# VoltageRegulators.net
KiCad netlist of a schematic drawn in Altium Designer
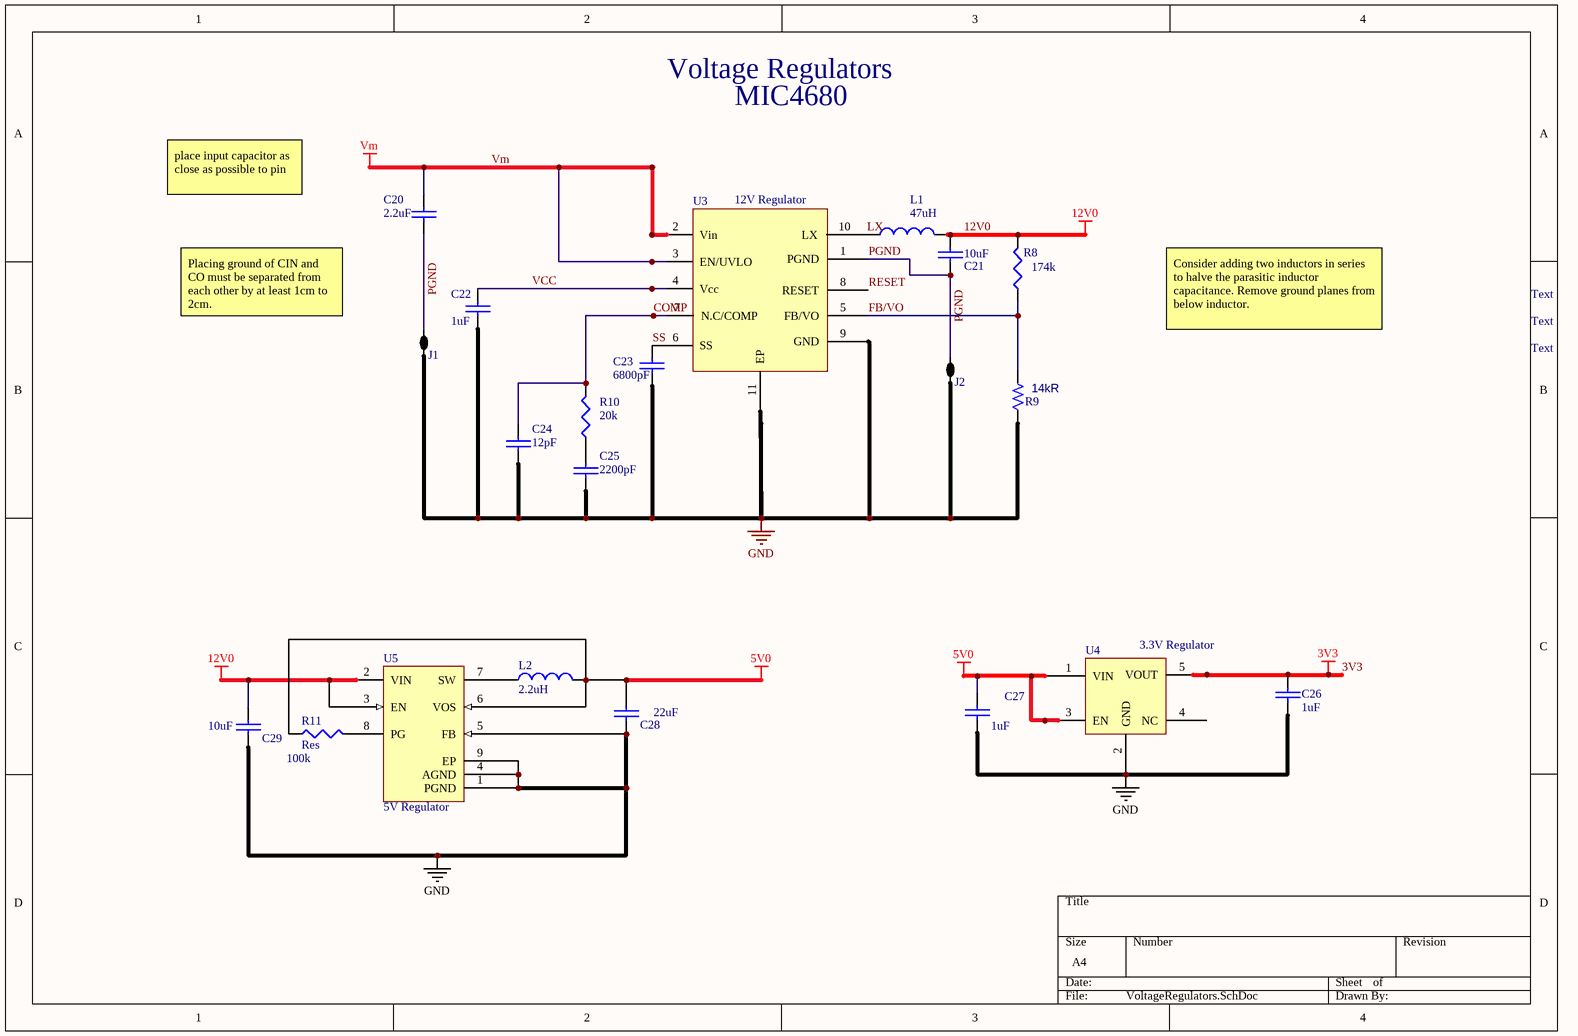
[diagram p0: VoltageRegulators.SchDoc]

(export (version "E")
  (design (tool "Eeschema 10.0.6"))
  (components
    (comp (ref "C20")
      (value "2.2uF")
      (footprint "CAP0805")
      (description "Capacitor")
      (fields
        (field (name "MANUFACTURER") "TDK Corporation")
        (field (name "MANUFACTURER PART NUMBER") "C2012X7R1V225K085AC")
      )
      (libsource (lib "BPL-ShematicLibrary") (part "Capacitor"))
    )
    (comp (ref "C21")
      (value "10uF")
      (footprint "CAP1210")
      (description "Capacitor")
      (fields
        (field (name "MANUFACTURER") "KEMET")
        (field (name "MANUFACTURER PART NUMBER") "C1210C106K9RAC7800")
      )
      (libsource (lib "BPL-ShematicLibrary") (part "Capacitor"))
    )
    (comp (ref "C22")
      (value "1uF")
      (footprint "CAP0402")
      (description "Capacitor")
      (fields
        (field (name "MANUFACTURER") "TDK Corporation")
        (field (name "MANUFACTURER PART NUMBER") "C1005X5R1V105K050BC")
      )
      (libsource (lib "BPL-ShematicLibrary") (part "Capacitor"))
    )
    (comp (ref "C23")
      (value "6800pF")
      (footprint "CAP0402")
      (description "Capacitor")
      (fields
        (field (name "MANUFACTURER") "KEMET")
        (field (name "MANUFACTURER PART NUMBER") "C0402C682J5RACTU")
      )
      (libsource (lib "BPL-ShematicLibrary") (part "Capacitor"))
    )
    (comp (ref "C24")
      (value "12pF")
      (footprint "CAP0402")
      (description "Capacitor")
      (fields
        (field (name "MANUFACTURER") "KEMET")
        (field (name "MANUFACTURER PART NUMBER") "C0402C120J3GACAUTO")
      )
      (libsource (lib "BPL-ShematicLibrary") (part "Capacitor"))
    )
    (comp (ref "C25")
      (value "2200pF")
      (footprint "CAP0402")
      (description "Capacitor")
      (fields
        (field (name "MANUFACTURER") "Murata Electronics North America")
        (field (name "MANUFACTURER PART NUMBER") "GRM155R71H222KA01D")
      )
      (libsource (lib "BPL-ShematicLibrary") (part "Capacitor"))
    )
    (comp (ref "C26")
      (value "1uF")
      (footprint "CAP0402")
      (description "Capacitor")
      (fields
        (field (name "MANUFACTURER") "TDK Corporation")
        (field (name "MANUFACTURER PART NUMBER") "C1005X5R1V105K050BC")
      )
      (libsource (lib "BPL-ShematicLibrary") (part "Capacitor"))
    )
    (comp (ref "C27")
      (value "1uF")
      (footprint "CAP0402")
      (description "Capacitor")
      (fields
        (field (name "MANUFACTURER") "TDK Corporation")
        (field (name "MANUFACTURER PART NUMBER") "C1005X5R1V105K050BC")
      )
      (libsource (lib "BPL-ShematicLibrary") (part "Capacitor"))
    )
    (comp (ref "C28")
      (value "22uF")
      (footprint "CAP0805")
      (description "Capacitor")
      (fields
        (field (name "MANUFACTURER") "TDK Corporation")
        (field (name "MANUFACTURER PART NUMBER") "C2012X5R0J226K125AB")
      )
      (libsource (lib "BPL-ShematicLibrary") (part "Capacitor"))
    )
    (comp (ref "C29")
      (value "10uF")
      (footprint "CAP0805")
      (description "Capacitor")
      (fields
        (field (name "MANUFACTURER") "Murata Electronics North America")
        (field (name "MANUFACTURER PART NUMBER") "GRM21BR61E106MA73L")
      )
      (libsource (lib "BPL-ShematicLibrary") (part "Capacitor"))
    )
    (comp (ref "J1")
      (value "2 way net tie junction")
      (footprint "2way_LP")
      (libsource (lib "NetTieLib") (part "2way"))
    )
    (comp (ref "J2")
      (value "2 way net tie junction")
      (footprint "2way_LP")
      (libsource (lib "NetTieLib") (part "2way"))
    )
    (comp (ref "L1")
      (value "47uH")
      (footprint "74404064470")
      (description "FIXED IND 47UH 1.2A 200 MOHM SMD")
      (fields
        (field (name "MANUFACTURER") "Wurth Electronics Inc.")
        (field (name "MANUFACTURER PART NUMBER") "74404064470")
      )
      (libsource (lib "BPL-ShematicLibrary") (part "Inductor"))
    )
    (comp (ref "L2")
      (value "2.2uH")
      (footprint "VLS3012HBX")
      (description "FIXED IND 2.2UH 3.15A 106 MOHM")
      (fields
        (field (name "MANUFACTURER") "TDK Corporation")
        (field (name "MANUFACTURER PART NUMBER") "VLS3012HBX-2R2M")
      )
      (libsource (lib "BPL-ShematicLibrary") (part "Inductor"))
    )
    (comp (ref "R8")
      (value "174k")
      (footprint "RES0402")
      (description "Resistor")
      (fields
        (field (name "MANUFACTURER") "Yageo")
        (field (name "MANUFACTURER PART NUMBER") "RC0402FR-07174KL")
      )
      (libsource (lib "") (part "Resistor_1"))
    )
    (comp (ref "R9")
      (value "Resistor")
      (footprint "RES0402")
      (description "RES SMD 14K OHM 1% 1/16W 0402")
      (fields (field (name "RESISTANCE") "14kR") (field (name "TOLERANCE") "1%"))
      (libsource (lib "BPL-ShematicLibrary") (part "Resistor"))
    )
    (comp (ref "R10")
      (value "20k")
      (footprint "RES0402")
      (description "Resistor")
      (fields
        (field (name "MANUFACTURER") "Yageo")
        (field (name "MANUFACTURER PART NUMBER") "RT0402DRD0720KL")
      )
      (libsource (lib "") (part "Resistor_1"))
    )
    (comp (ref "R11")
      (value "Res")
      (footprint "RES0402")
      (description "Resistor")
      (fields
        (field (name "MANUFACTURER") "Yageo")
        (field (name "MANUFACTURER PART NUMBER") "RC0402FR-07100KL")
        (field (name "ALTIUM_VALUE") "100k")
      )
      (libsource (lib "") (part "Resistor_1"))
    )
    (comp (ref "U3")
      (value "12V Regulator")
      (footprint "L10 3x2 0.5mm Pitch")
      (description "60V, 1A, Ultra-Small, High-Efficiency,  Synchronous Step-Down DC-DC Converter")
      (fields
        (field (name "MANUFACTURER") "Maxim Integrated")
        (field (name "MANUFACTURER PART NUMBER") "MAX17502GATB+T")
      )
      (libsource (lib "BPL-ShematicLibrary") (part "MAX17502G"))
    )
    (comp (ref "U4")
      (value "3.3V Regulator")
      (footprint "SOT23-5")
      (description "MIC5504_SOT23-5")
      (fields
        (field (name "MANUFACTURER") "Microchip Technology")
        (field (name "MANUFACTURER PART NUMBER") "MIC5504-3.3YM5-TR")
      )
      (libsource (lib "BPL-ShematicLibrary") (part "MIC5501_SOT23-5"))
    )
    (comp (ref "U5")
      (value "5V Regulator")
      (footprint "DSG8-1600X900TP")
      (fields (field (name "MANUFACTURER") "Texas Instruments") (field (name "PARTNUMBER") "TPS62163DSGR"))
      (libsource (lib "TI Power Management Step-Down Regulator") (part "TPS62163DSGR"))
    )
  )
  (nets
    (net (code "1") (name "/COMP") (class "Default")
      (node (ref "C24") (pin "1") (pinfunction "1_1") (pintype "passive"))
      (node (ref "R10") (pin "2") (pinfunction "2_2") (pintype "passive"))
      (node (ref "U3") (pin "7") (pinfunction "N.C/COMP_7") (pintype "passive"))
    )
    (net (code "2") (name "/FB{slash}VO") (class "Default")
      (node (ref "R8") (pin "1") (pinfunction "1_1") (pintype "passive"))
      (node (ref "R9") (pin "2") (pinfunction "2_2") (pintype "passive"))
      (node (ref "U3") (pin "5") (pinfunction "FB/VO_5") (pintype "passive"))
    )
    (net (code "3") (name "/LX") (class "Default")
      (node (ref "L1") (pin "1") (pinfunction "1_1") (pintype "passive"))
      (node (ref "U3") (pin "10") (pinfunction "LX_10") (pintype "passive"))
    )
    (net (code "4") (name "/PGND") (class "Default")
      (node (ref "C20") (pin "2") (pinfunction "2_2") (pintype "passive"))
      (node (ref "C21") (pin "2") (pinfunction "2_2") (pintype "passive"))
      (node (ref "J1") (pin "2") (pinfunction "2_2") (pintype "passive"))
      (node (ref "J2") (pin "2") (pinfunction "2_2") (pintype "passive"))
      (node (ref "U3") (pin "1") (pinfunction "PGND_1") (pintype "passive"))
    )
    (net (code "5") (name "/RESET") (class "Default")
      (node (ref "U3") (pin "8") (pinfunction "RESET_8") (pintype "passive"))
    )
    (net (code "6") (name "/SS") (class "Default")
      (node (ref "C23") (pin "1") (pinfunction "1_1") (pintype "passive"))
      (node (ref "U3") (pin "6") (pinfunction "SS_6") (pintype "passive"))
    )
    (net (code "7") (name "/VCC") (class "Default")
      (node (ref "C22") (pin "1") (pinfunction "1_1") (pintype "passive"))
      (node (ref "U3") (pin "4") (pinfunction "Vcc_4") (pintype "passive"))
    )
    (net (code "8") (name "3V3") (class "Default")
      (node (ref "C26") (pin "1") (pinfunction "1_1") (pintype "passive"))
      (node (ref "U4") (pin "5") (pinfunction "VOUT_5") (pintype "passive"))
    )
    (net (code "9") (name "5V0") (class "Default")
      (node (ref "C27") (pin "1") (pinfunction "1_1") (pintype "passive"))
      (node (ref "C28") (pin "1") (pinfunction "1_1") (pintype "passive"))
      (node (ref "L2") (pin "2") (pinfunction "2_2") (pintype "passive"))
      (node (ref "R11") (pin "1") (pinfunction "1_1") (pintype "passive"))
      (node (ref "U4") (pin "1") (pinfunction "VIN_1") (pintype "passive"))
      (node (ref "U4") (pin "3") (pinfunction "EN_3") (pintype "passive"))
      (node (ref "U5") (pin "6") (pinfunction "VOS_6") (pintype "input"))
    )
    (net (code "10") (name "12V0") (class "Default")
      (node (ref "C21") (pin "1") (pinfunction "1_1") (pintype "passive"))
      (node (ref "C29") (pin "1") (pinfunction "1_1") (pintype "passive"))
      (node (ref "L1") (pin "2") (pinfunction "2_2") (pintype "passive"))
      (node (ref "R8") (pin "2") (pinfunction "2_2") (pintype "passive"))
      (node (ref "U5") (pin "2") (pinfunction "VIN_2") (pintype "power_in"))
      (node (ref "U5") (pin "3") (pinfunction "EN_3") (pintype "input"))
    )
    (net (code "11") (name "GND") (class "Default")
      (node (ref "C22") (pin "2") (pinfunction "2_2") (pintype "passive"))
      (node (ref "C23") (pin "2") (pinfunction "2_2") (pintype "passive"))
      (node (ref "C24") (pin "2") (pinfunction "2_2") (pintype "passive"))
      (node (ref "C25") (pin "2") (pinfunction "2_2") (pintype "passive"))
      (node (ref "C26") (pin "2") (pinfunction "2_2") (pintype "passive"))
      (node (ref "C27") (pin "2") (pinfunction "2_2") (pintype "passive"))
      (node (ref "C28") (pin "2") (pinfunction "2_2") (pintype "passive"))
      (node (ref "C29") (pin "2") (pinfunction "2_2") (pintype "passive"))
      (node (ref "J1") (pin "1") (pinfunction "1_1") (pintype "passive"))
      (node (ref "J2") (pin "1") (pinfunction "1_1") (pintype "passive"))
      (node (ref "R9") (pin "1") (pinfunction "1_1") (pintype "passive"))
      (node (ref "U3") (pin "11") (pinfunction "EP_11") (pintype "passive"))
      (node (ref "U3") (pin "9") (pinfunction "GND_9") (pintype "passive"))
      (node (ref "U4") (pin "2") (pinfunction "GND_2") (pintype "passive"))
      (node (ref "U5") (pin "1") (pinfunction "PGND_1") (pintype "power_in"))
      (node (ref "U5") (pin "4") (pinfunction "AGND_4") (pintype "power_in"))
      (node (ref "U5") (pin "5") (pinfunction "FB_5") (pintype "input"))
      (node (ref "U5") (pin "9") (pinfunction "EP_9") (pintype "power_in"))
    )
    (net (code "12") (name "Net-(C25-Pad1)") (class "Default")
      (node (ref "C25") (pin "1") (pinfunction "1_1") (pintype "passive"))
      (node (ref "R10") (pin "1") (pinfunction "1_1") (pintype "passive"))
    )
    (net (code "13") (name "Net-(U5-PG)") (class "Default")
      (node (ref "R11") (pin "2") (pinfunction "2_2") (pintype "passive"))
      (node (ref "U5") (pin "8") (pinfunction "PG_8") (pintype "tri_state"))
    )
    (net (code "14") (name "Net-(U5-SW)") (class "Default")
      (node (ref "L2") (pin "1") (pinfunction "1_1") (pintype "passive"))
      (node (ref "U5") (pin "7") (pinfunction "SW_7") (pintype "power_in"))
    )
    (net (code "15") (name "Vm") (class "Default")
      (node (ref "C20") (pin "1") (pinfunction "1_1") (pintype "passive"))
      (node (ref "U3") (pin "2") (pinfunction "Vin_2") (pintype "passive"))
      (node (ref "U3") (pin "3") (pinfunction "EN/UVLO_3") (pintype "passive"))
    )
    (net (code "16") (name "unconnected-(U4-NC-Pad4)") (class "Default")
      (node (ref "U4") (pin "4") (pinfunction "NC_4") (pintype "passive"))
    )
  )
)
